# PowerR3.net
KiCad netlist of a schematic drawn in Altium Designer
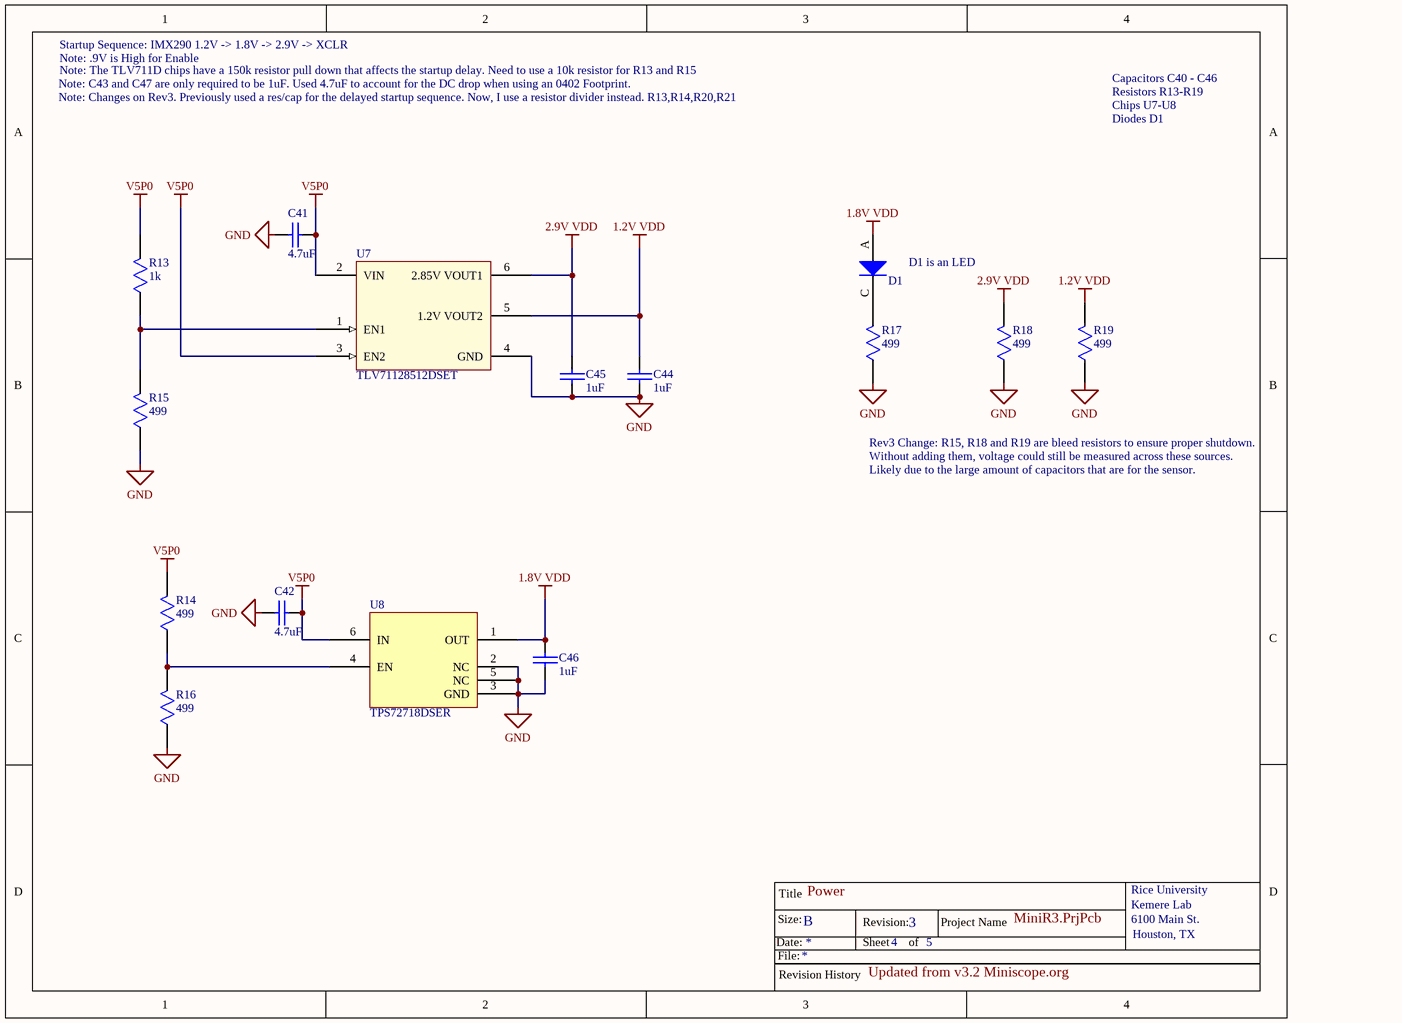
[diagram p0: PowerR3.SchDoc]

(export (version "E")
  (design (tool "Eeschema 10.0.6"))
  (components
    (comp (ref "C41")
      (value "4.7uF")
      (footprint "SMD CAP 0402")
      (libsource (lib "DA_Component_Library") (part "Capacitor"))
    )
    (comp (ref "C42")
      (value "4.7uF")
      (footprint "SMD CAP 0402")
      (libsource (lib "DA_Component_Library") (part "Capacitor"))
    )
    (comp (ref "C44")
      (value "1uF")
      (footprint "SMD CAP 0402")
      (libsource (lib "DA_Component_Library") (part "Capacitor"))
    )
    (comp (ref "C45")
      (value "1uF")
      (footprint "SMD CAP 0402")
      (libsource (lib "DA_Component_Library") (part "Capacitor"))
    )
    (comp (ref "C46")
      (value "1uF")
      (footprint "SMD CAP 0402")
      (libsource (lib "DA_Component_Library") (part "Capacitor"))
    )
    (comp (ref "D1")
      (value "LED 0603")
      (footprint "LED_0603")
      (description "LTST_C195TBJRKT")
      (libsource (lib "DA_Component_Library") (part "LED 0603"))
    )
    (comp (ref "R13")
      (value "1k")
      (footprint "SMD RES 0402")
      (libsource (lib "DA_Component_Library") (part "Resistor"))
    )
    (comp (ref "R14")
      (value "499")
      (footprint "SMD RES 0402")
      (libsource (lib "DA_Component_Library") (part "Resistor"))
    )
    (comp (ref "R15")
      (value "499")
      (footprint "SMD RES 0402")
      (libsource (lib "DA_Component_Library") (part "Resistor"))
    )
    (comp (ref "R16")
      (value "499")
      (footprint "SMD RES 0402")
      (libsource (lib "DA_Component_Library") (part "Resistor"))
    )
    (comp (ref "R17")
      (value "499")
      (footprint "SMD RES 0402")
      (libsource (lib "DA_Component_Library") (part "Resistor"))
    )
    (comp (ref "R18")
      (value "499")
      (footprint "SMD RES 0402")
      (libsource (lib "DA_Component_Library") (part "Resistor"))
    )
    (comp (ref "R19")
      (value "499")
      (footprint "SMD RES 0402")
      (libsource (lib "DA_Component_Library") (part "Resistor"))
    )
    (comp (ref "U7")
      (value "TLV71128512DSET")
      (footprint "DSE")
      (description "Dual 2.85V and 1.2V Linear Regulator")
      (libsource (lib "Miniscope") (part "TLV71128512DSET"))
    )
    (comp (ref "U8")
      (value "TPS72718DSER")
      (footprint "DSE")
      (description "Single 1.8V Linear Regulator")
      (libsource (lib "Miniscope") (part "TPS72718DSER"))
    )
  )
  (nets
    (net (code "1") (name "1.2V VDD") (class "Default")
      (node (ref "C44") (pin "0") (pinfunction "0_0") (pintype "passive"))
      (node (ref "R19") (pin "1") (pinfunction "1_1") (pintype "passive"))
      (node (ref "U7") (pin "5") (pinfunction "1.2V_VOUT2_5") (pintype "power_in"))
    )
    (net (code "2") (name "1.8V VDD") (class "Default")
      (node (ref "C46") (pin "1") (pinfunction "1_1") (pintype "passive"))
      (node (ref "D1") (pin "A") (pinfunction "A_A") (pintype "passive"))
      (node (ref "U8") (pin "1") (pinfunction "OUT_1") (pintype "power_in"))
    )
    (net (code "3") (name "2.9V VDD") (class "Default")
      (node (ref "C45") (pin "0") (pinfunction "0_0") (pintype "passive"))
      (node (ref "R18") (pin "1") (pinfunction "1_1") (pintype "passive"))
      (node (ref "U7") (pin "6") (pinfunction "2.85V_VOUT1_6") (pintype "power_in"))
    )
    (net (code "4") (name "GND") (class "Default")
      (node (ref "C41") (pin "1") (pinfunction "1_1") (pintype "passive"))
      (node (ref "C42") (pin "0") (pinfunction "0_0") (pintype "passive"))
      (node (ref "C44") (pin "1") (pinfunction "1_1") (pintype "passive"))
      (node (ref "C45") (pin "1") (pinfunction "1_1") (pintype "passive"))
      (node (ref "C46") (pin "0") (pinfunction "0_0") (pintype "passive"))
      (node (ref "R15") (pin "0") (pinfunction "0_0") (pintype "passive"))
      (node (ref "R16") (pin "0") (pinfunction "0_0") (pintype "passive"))
      (node (ref "R17") (pin "0") (pinfunction "0_0") (pintype "passive"))
      (node (ref "R18") (pin "0") (pinfunction "0_0") (pintype "passive"))
      (node (ref "R19") (pin "0") (pinfunction "0_0") (pintype "passive"))
      (node (ref "U7") (pin "4") (pinfunction "GND_4") (pintype "power_in"))
      (node (ref "U8") (pin "2") (pinfunction "NC_2") (pintype "passive"))
      (node (ref "U8") (pin "3") (pinfunction "GND_3") (pintype "power_in"))
      (node (ref "U8") (pin "5") (pinfunction "NC_5") (pintype "power_in"))
    )
    (net (code "5") (name "Net-(D1-PadC)") (class "Default")
      (node (ref "D1") (pin "C") (pinfunction "C_C") (pintype "passive"))
      (node (ref "R17") (pin "1") (pinfunction "1_1") (pintype "passive"))
    )
    (net (code "6") (name "Net-(U7-EN1)") (class "Default")
      (node (ref "R13") (pin "0") (pinfunction "0_0") (pintype "passive"))
      (node (ref "R15") (pin "1") (pinfunction "1_1") (pintype "passive"))
      (node (ref "U7") (pin "1") (pinfunction "EN1_1") (pintype "input"))
    )
    (net (code "7") (name "Net-(U8-EN)") (class "Default")
      (node (ref "R14") (pin "0") (pinfunction "0_0") (pintype "passive"))
      (node (ref "R16") (pin "1") (pinfunction "1_1") (pintype "passive"))
      (node (ref "U8") (pin "4") (pinfunction "EN_4") (pintype "power_in"))
    )
    (net (code "8") (name "V5P0") (class "Default")
      (node (ref "C41") (pin "0") (pinfunction "0_0") (pintype "passive"))
      (node (ref "C42") (pin "1") (pinfunction "1_1") (pintype "passive"))
      (node (ref "R13") (pin "1") (pinfunction "1_1") (pintype "passive"))
      (node (ref "R14") (pin "1") (pinfunction "1_1") (pintype "passive"))
      (node (ref "U7") (pin "2") (pinfunction "VIN_2") (pintype "power_in"))
      (node (ref "U7") (pin "3") (pinfunction "EN2_3") (pintype "input"))
      (node (ref "U8") (pin "6") (pinfunction "IN_6") (pintype "power_in"))
    )
  )
)
